# CH32V00x_Touch_Kit.net
KiCad netlist of a schematic drawn in Altium Designer
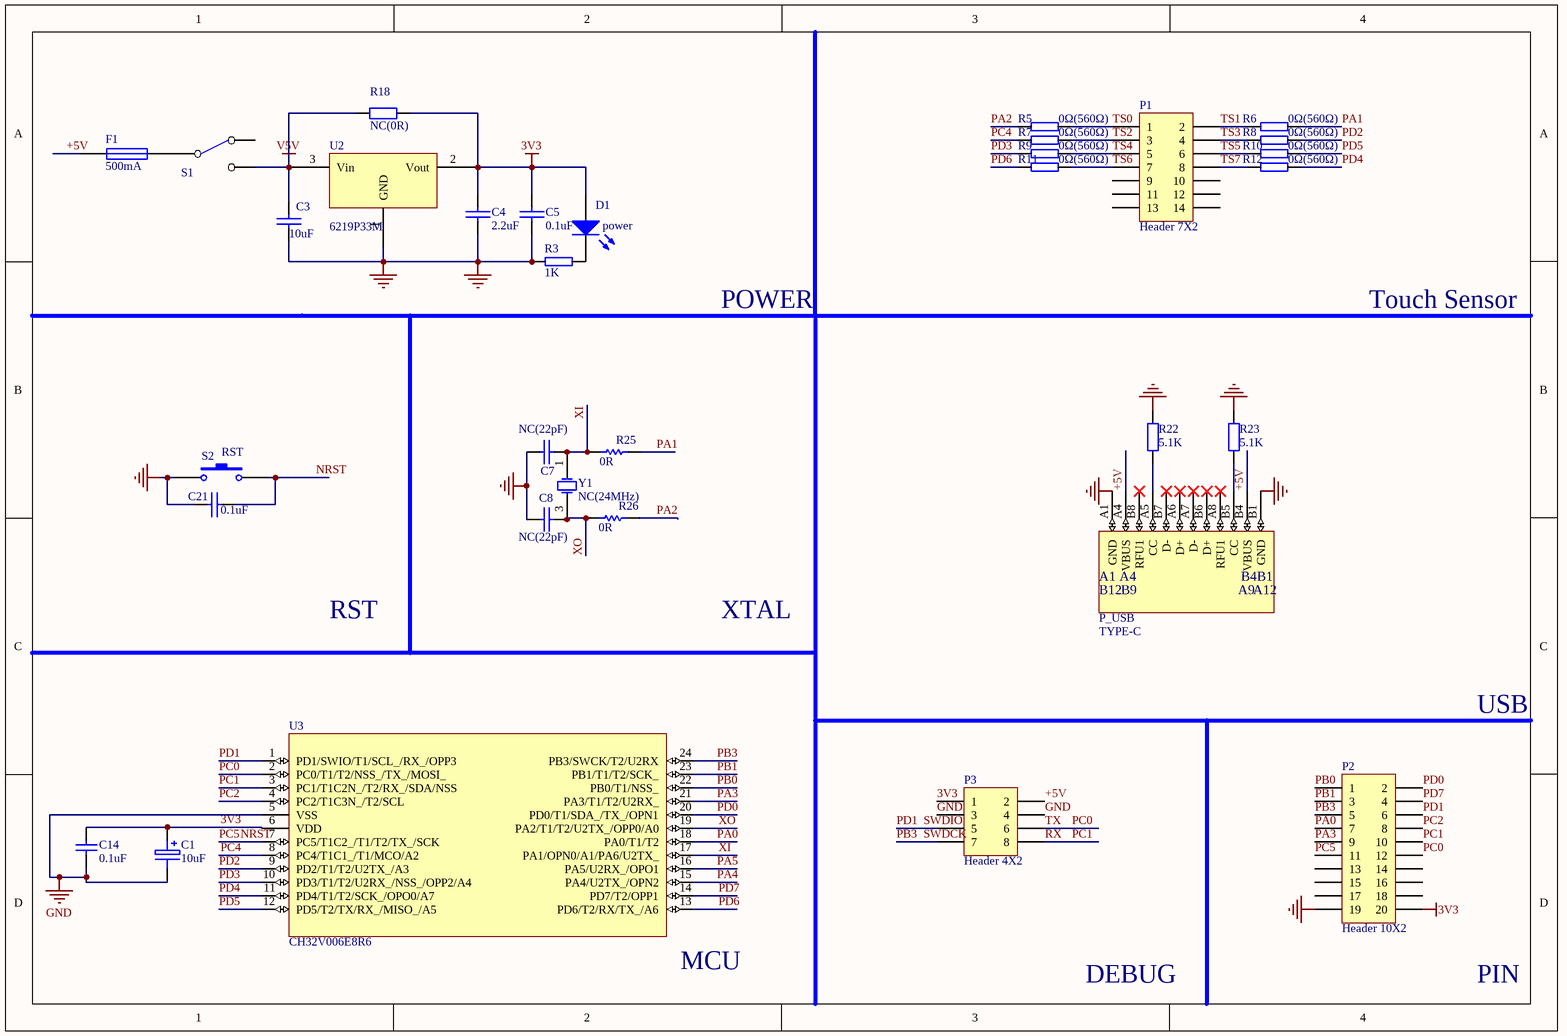
[diagram p0: CH32V00x_Touch_Kit.SchDoc]

(export (version "E")
  (design (tool "Eeschema 10.0.6"))
  (components
    (comp (ref "C1") (value "10uF") (footprint "CASE-A_3216") (libsource (lib "电阻电容") (part "T-A/4.7uF/16V")))
    (comp (ref "C3")
      (value "10uF")
      (footprint "0603_C")
      (description "Capacitor")
      (libsource (lib "") (part "CAP_1"))
    )
    (comp (ref "C4")
      (value "2.2uF")
      (footprint "0402_C")
      (description "Capacitor")
      (libsource (lib "") (part "CAP_1"))
    )
    (comp (ref "C5")
      (value "0.1uF")
      (footprint "0402_C")
      (description "Capacitor")
      (libsource (lib "") (part "CAP_1"))
    )
    (comp (ref "C7")
      (value "NC(22pF)")
      (footprint "0402_C")
      (description "Capacitor")
      (libsource (lib "") (part "CAP_1"))
    )
    (comp (ref "C8")
      (value "NC(22pF)")
      (footprint "0402_C")
      (description "Capacitor")
      (libsource (lib "") (part "CAP_1"))
    )
    (comp (ref "C14")
      (value "0.1uF")
      (footprint "0402_C")
      (description "Capacitor")
      (fields (field (name "PUBLISHER") "Altium Limited"))
      (libsource (lib "*") (part "Cap"))
    )
    (comp (ref "C21")
      (value "0.1uF")
      (footprint "0402_C")
      (description "Capacitor")
      (libsource (lib "*") (part "CAP"))
    )
    (comp (ref "D1")
      (value "power")
      (footprint "0603+")
      (description "Typical INFRARED GaAs LED")
      (fields (field (name "PUBLISHER") "Altium Limited"))
      (libsource (lib "*") (part "LED0"))
    )
    (comp (ref "F1")
      (value "500mA")
      (footprint "0603")
      (description "Fuse")
      (libsource (lib "wch_sch_others") (part "FUSE1"))
    )
    (comp (ref "P1")
      (value "Header 7X2")
      (footprint "HDR-TH_14P-P2.54-H-M-R2-C10-S2.54")
      (description "Header, 7-Pin, Dual row")
      (fields (field (name "PUBLISHER") "Altium Limited"))
      (libsource (lib "Miscellaneous Connectors") (part "Header 7X2"))
    )
    (comp (ref "P2")
      (value "Header 10X2")
      (footprint "HDR-TH_20P-P2.54-H-M-R2-C10-S2.54")
      (description "Header, 10-Pin, Dual row")
      (fields (field (name "PUBLISHER") "Altium Limited"))
      (libsource (lib "Miscellaneous Connectors") (part "Header 10X2"))
    )
    (comp (ref "P3")
      (value "Header 4X2")
      (footprint "IDC8-2.54mm")
      (description "Header, 4-Pin, Dual row")
      (fields (field (name "PUBLISHER") "Altium Limited"))
      (libsource (lib "Miscellaneous Connectors") (part "Header 4X2"))
    )
    (comp (ref "P_USB")
      (value "TYPE-C")
      (footprint "TYPE-C-Receptacle-2.0")
      (libsource (lib "*") (part "TYPE-C1"))
    )
    (comp (ref "R3") (value "1K") (footprint "0402") (libsource (lib "wch_sch_others") (part "RES")))
    (comp (ref "R5") (value "0Ω(560Ω)") (footprint "0402") (libsource (lib "wch_sch_others") (part "RES")))
    (comp (ref "R6") (value "0Ω(560Ω)") (footprint "0402") (libsource (lib "wch_sch_others") (part "RES")))
    (comp (ref "R7") (value "0Ω(560Ω)") (footprint "0402") (libsource (lib "wch_sch_others") (part "RES")))
    (comp (ref "R8") (value "0Ω(560Ω)") (footprint "0402") (libsource (lib "wch_sch_others") (part "RES")))
    (comp (ref "R9") (value "0Ω(560Ω)") (footprint "0402") (libsource (lib "wch_sch_others") (part "RES")))
    (comp (ref "R10") (value "0Ω(560Ω)") (footprint "0402") (libsource (lib "wch_sch_others") (part "RES")))
    (comp (ref "R11") (value "0Ω(560Ω)") (footprint "0402") (libsource (lib "wch_sch_others") (part "RES")))
    (comp (ref "R12") (value "0Ω(560Ω)") (footprint "0402") (libsource (lib "wch_sch_others") (part "RES")))
    (comp (ref "R18")
      (value "NC(0R)")
      (footprint "0402")
      (description "Resistor")
      (fields (field (name "PUBLISHER") "Altium Limited"))
      (libsource (lib "Miscellaneous Devices") (part "Res2"))
    )
    (comp (ref "R22")
      (value "5.1K")
      (footprint "0402")
      (description "Resistor")
      (libsource (lib "") (part "Res2_1"))
    )
    (comp (ref "R23")
      (value "5.1K")
      (footprint "0402")
      (description "Resistor")
      (libsource (lib "") (part "Res2_1"))
    )
    (comp (ref "R25")
      (value "0R")
      (footprint "0402")
      (description "Semiconductor Resistor")
      (fields (field (name "PUBLISHER") "Altium Limited"))
      (libsource (lib "*") (part "Res Semi"))
    )
    (comp (ref "R26")
      (value "0R")
      (footprint "0402")
      (description "Semiconductor Resistor")
      (fields (field (name "PUBLISHER") "Altium Limited"))
      (libsource (lib "*") (part "Res Semi"))
    )
    (comp (ref "S1") (value "SW SPDT") (footprint "SW1") (libsource (lib "*") (part "SW SPDT")))
    (comp (ref "S2")
      (value "RST")
      (footprint "SMD_6.1x3.65x2.5mm-KEY")
      (description "Switch")
      (fields (field (name "PUBLISHER") "Altium Limited"))
      (libsource (lib "*") (part "SW-PB"))
    )
    (comp (ref "U2")
      (value "6219P33M")
      (footprint "SOT-23")
      (libsource (lib "wch_sch_others") (part "6219P33M"))
    )
    (comp (ref "U3")
      (value "CH32V006E8R6")
      (footprint "QSOP24")
      (description "RISC-V MCU, 48MHz, ADC/OPA/CMP/2*UART/I2C/SPI")
      (libsource (lib "CHXXX") (part "CH32V006E8R6"))
    )
    (comp (ref "Y1")
      (value "NC(24MHz)")
      (footprint "XT3225")
      (description "Crystal Oscillator")
      (fields (field (name "PUBLISHER") "Altium Limited"))
      (libsource (lib "*") (part "XTAL"))
    )
  )
  (nets
    (net (code "1") (name "/+5V") (class "Default")
      (node (ref "F1") (pin "1") (pinfunction "1_1") (pintype "passive"))
      (node (ref "P3") (pin "2") (pinfunction "2_2") (pintype "passive"))
      (node (ref "P_USB") (pin "A4") (pinfunction "VBUS_A4") (pintype "bidirectional"))
      (node (ref "P_USB") (pin "B4") (pinfunction "VBUS_B4") (pintype "bidirectional"))
    )
    (net (code "2") (name "/NRST") (class "Default")
      (node (ref "C21") (pin "2") (pinfunction "2_2") (pintype "passive"))
      (node (ref "P2") (pin "11") (pinfunction "11_11") (pintype "passive"))
      (node (ref "S2") (pin "2") (pinfunction "2_2") (pintype "passive"))
      (node (ref "U3") (pin "7") (pinfunction "PC5/T1C2_/T1/T2/TX_/SCK_7") (pintype "bidirectional"))
    )
    (net (code "3") (name "/PA0") (class "Default")
      (node (ref "P2") (pin "7") (pinfunction "7_7") (pintype "passive"))
      (node (ref "U3") (pin "18") (pinfunction "PA0/T1/T2_18") (pintype "bidirectional"))
    )
    (net (code "4") (name "/PA1") (class "Default")
      (node (ref "R25") (pin "2") (pinfunction "2_2") (pintype "passive"))
      (node (ref "R6") (pin "2") (pintype "passive"))
    )
    (net (code "5") (name "/PA2") (class "Default")
      (node (ref "R26") (pin "2") (pinfunction "2_2") (pintype "passive"))
      (node (ref "R5") (pin "1") (pintype "passive"))
    )
    (net (code "6") (name "/PA3") (class "Default")
      (node (ref "P2") (pin "9") (pinfunction "9_9") (pintype "passive"))
      (node (ref "U3") (pin "21") (pinfunction "PA3/T1/T2/U2RX__21") (pintype "bidirectional"))
    )
    (net (code "7") (name "/PA4") (class "Default")
      (node (ref "U3") (pin "15") (pinfunction "PA4/U2TX_/OPN2_15") (pintype "bidirectional"))
    )
    (net (code "8") (name "/PA5") (class "Default")
      (node (ref "U3") (pin "16") (pinfunction "PA5/U2RX_/OPO1_16") (pintype "bidirectional"))
    )
    (net (code "9") (name "/PB0") (class "Default")
      (node (ref "P2") (pin "1") (pinfunction "1_1") (pintype "passive"))
      (node (ref "U3") (pin "22") (pinfunction "PB0/T1/NSS__22") (pintype "bidirectional"))
    )
    (net (code "10") (name "/PB1") (class "Default")
      (node (ref "P2") (pin "3") (pinfunction "3_3") (pintype "passive"))
      (node (ref "U3") (pin "23") (pinfunction "PB1/T1/T2/SCK__23") (pintype "bidirectional"))
    )
    (net (code "11") (name "/PB3") (class "Default")
      (node (ref "P2") (pin "5") (pinfunction "5_5") (pintype "passive"))
      (node (ref "P3") (pin "7") (pinfunction "7_7") (pintype "passive"))
      (node (ref "U3") (pin "24") (pinfunction "PB3/SWCK/T2/U2RX_24") (pintype "bidirectional"))
    )
    (net (code "12") (name "/PC0") (class "Default")
      (node (ref "P2") (pin "12") (pinfunction "12_12") (pintype "passive"))
      (node (ref "P3") (pin "6") (pinfunction "6_6") (pintype "passive"))
      (node (ref "U3") (pin "2") (pinfunction "PC0/T1/T2/NSS_/TX_/MOSI__2") (pintype "bidirectional"))
    )
    (net (code "13") (name "/PC1") (class "Default")
      (node (ref "P2") (pin "10") (pinfunction "10_10") (pintype "passive"))
      (node (ref "P3") (pin "8") (pinfunction "8_8") (pintype "passive"))
      (node (ref "U3") (pin "3") (pinfunction "PC1/T1C2N_/T2/RX_/SDA/NSS_3") (pintype "bidirectional"))
    )
    (net (code "14") (name "/PC2") (class "Default")
      (node (ref "P2") (pin "8") (pinfunction "8_8") (pintype "passive"))
      (node (ref "U3") (pin "4") (pinfunction "PC2/T1C3N_/T2/SCL_4") (pintype "bidirectional"))
    )
    (net (code "15") (name "/PC4") (class "Default")
      (node (ref "R7") (pin "1") (pintype "passive"))
      (node (ref "U3") (pin "8") (pinfunction "PC4/T1C1_/T1/MCO/A2_8") (pintype "bidirectional"))
    )
    (net (code "16") (name "/PD0") (class "Default")
      (node (ref "P2") (pin "2") (pinfunction "2_2") (pintype "passive"))
      (node (ref "U3") (pin "20") (pinfunction "PD0/T1/SDA_/TX_/OPN1_20") (pintype "bidirectional"))
    )
    (net (code "17") (name "/PD1") (class "Default")
      (node (ref "P2") (pin "6") (pinfunction "6_6") (pintype "passive"))
      (node (ref "P3") (pin "5") (pinfunction "5_5") (pintype "passive"))
      (node (ref "U3") (pin "1") (pinfunction "PD1/SWIO/T1/SCL_/RX_/OPP3_1") (pintype "bidirectional"))
    )
    (net (code "18") (name "/PD2") (class "Default")
      (node (ref "R8") (pin "2") (pintype "passive"))
      (node (ref "U3") (pin "9") (pinfunction "PD2/T1/T2/U2TX_/A3_9") (pintype "bidirectional"))
    )
    (net (code "19") (name "/PD3") (class "Default")
      (node (ref "R9") (pin "1") (pintype "passive"))
      (node (ref "U3") (pin "10") (pinfunction "PD3/T1/T2/U2RX_/NSS_/OPP2/A4_10") (pintype "bidirectional"))
    )
    (net (code "20") (name "/PD4") (class "Default")
      (node (ref "R12") (pin "2") (pintype "passive"))
      (node (ref "U3") (pin "11") (pinfunction "PD4/T1/T2/SCK_/OPO0/A7_11") (pintype "bidirectional"))
    )
    (net (code "21") (name "/PD5") (class "Default")
      (node (ref "R10") (pin "2") (pintype "passive"))
      (node (ref "U3") (pin "12") (pinfunction "PD5/T2/TX/RX_/MISO_/A5_12") (pintype "bidirectional"))
    )
    (net (code "22") (name "/PD6") (class "Default")
      (node (ref "R11") (pin "1") (pintype "passive"))
      (node (ref "U3") (pin "13") (pinfunction "PD6/T2/RX/TX_/A6_13") (pintype "bidirectional"))
    )
    (net (code "23") (name "/PD7") (class "Default")
      (node (ref "P2") (pin "4") (pinfunction "4_4") (pintype "passive"))
      (node (ref "U3") (pin "14") (pinfunction "PD7/T2/OPP1_14") (pintype "bidirectional"))
    )
    (net (code "24") (name "/TS0") (class "Default")
      (node (ref "P1") (pin "1") (pinfunction "1_1") (pintype "passive"))
      (node (ref "R5") (pin "2") (pintype "passive"))
    )
    (net (code "25") (name "/TS1") (class "Default")
      (node (ref "P1") (pin "2") (pinfunction "2_2") (pintype "passive"))
      (node (ref "R6") (pin "1") (pintype "passive"))
    )
    (net (code "26") (name "/TS2") (class "Default")
      (node (ref "P1") (pin "3") (pinfunction "3_3") (pintype "passive"))
      (node (ref "R7") (pin "2") (pintype "passive"))
    )
    (net (code "27") (name "/TS3") (class "Default")
      (node (ref "P1") (pin "4") (pinfunction "4_4") (pintype "passive"))
      (node (ref "R8") (pin "1") (pintype "passive"))
    )
    (net (code "28") (name "/TS4") (class "Default")
      (node (ref "P1") (pin "5") (pinfunction "5_5") (pintype "passive"))
      (node (ref "R9") (pin "2") (pintype "passive"))
    )
    (net (code "29") (name "/TS5") (class "Default")
      (node (ref "P1") (pin "6") (pinfunction "6_6") (pintype "passive"))
      (node (ref "R10") (pin "1") (pintype "passive"))
    )
    (net (code "30") (name "/TS6") (class "Default")
      (node (ref "P1") (pin "7") (pinfunction "7_7") (pintype "passive"))
      (node (ref "R11") (pin "2") (pintype "passive"))
    )
    (net (code "31") (name "/TS7") (class "Default")
      (node (ref "P1") (pin "8") (pinfunction "8_8") (pintype "passive"))
      (node (ref "R12") (pin "1") (pintype "passive"))
    )
    (net (code "32") (name "/XI") (class "Default")
      (node (ref "C7") (pin "2") (pinfunction "2_2") (pintype "passive"))
      (node (ref "R25") (pin "1") (pinfunction "1_1") (pintype "passive"))
      (node (ref "U3") (pin "17") (pinfunction "PA1/OPN0/A1/PA6/U2TX__17") (pintype "bidirectional"))
      (node (ref "Y1") (pin "1") (pinfunction "OSC1_1") (pintype "passive"))
    )
    (net (code "33") (name "/XO") (class "Default")
      (node (ref "C8") (pin "2") (pinfunction "2_2") (pintype "passive"))
      (node (ref "R26") (pin "1") (pinfunction "1_1") (pintype "passive"))
      (node (ref "U3") (pin "19") (pinfunction "PA2/T1/T2/U2TX_/OPP0/A0_19") (pintype "bidirectional"))
      (node (ref "Y1") (pin "3") (pinfunction "OSC2_3") (pintype "passive"))
    )
    (net (code "34") (name "3V3") (class "Default")
      (node (ref "C1") (pin "1") (pinfunction "1_1") (pintype "passive"))
      (node (ref "C14") (pin "2") (pinfunction "2_2") (pintype "passive"))
      (node (ref "C4") (pin "1") (pinfunction "1_1") (pintype "passive"))
      (node (ref "C5") (pin "1") (pinfunction "1_1") (pintype "passive"))
      (node (ref "D1") (pin "1") (pinfunction "A_1") (pintype "passive"))
      (node (ref "P2") (pin "20") (pinfunction "20_20") (pintype "passive"))
      (node (ref "P3") (pin "1") (pinfunction "1_1") (pintype "passive"))
      (node (ref "R18") (pin "1") (pinfunction "1_1") (pintype "passive"))
      (node (ref "U2") (pin "2") (pinfunction "Vout_2") (pintype "passive"))
      (node (ref "U3") (pin "6") (pinfunction "VDD_6") (pintype "power_in"))
    )
    (net (code "35") (name "GND") (class "Default")
      (node (ref "C1") (pin "2") (pinfunction "2_2") (pintype "passive"))
      (node (ref "C14") (pin "1") (pinfunction "1_1") (pintype "passive"))
      (node (ref "C21") (pin "1") (pinfunction "1_1") (pintype "passive"))
      (node (ref "C3") (pin "2") (pinfunction "2_2") (pintype "passive"))
      (node (ref "C4") (pin "2") (pinfunction "2_2") (pintype "passive"))
      (node (ref "C5") (pin "2") (pinfunction "2_2") (pintype "passive"))
      (node (ref "C7") (pin "1") (pinfunction "1_1") (pintype "passive"))
      (node (ref "C8") (pin "1") (pinfunction "1_1") (pintype "passive"))
      (node (ref "P2") (pin "19") (pinfunction "19_19") (pintype "passive"))
      (node (ref "P3") (pin "3") (pinfunction "3_3") (pintype "passive"))
      (node (ref "P3") (pin "4") (pinfunction "4_4") (pintype "passive"))
      (node (ref "P_USB") (pin "A1") (pinfunction "GND_A1") (pintype "bidirectional"))
      (node (ref "P_USB") (pin "B1") (pinfunction "GND_B1") (pintype "bidirectional"))
      (node (ref "R22") (pin "2") (pinfunction "2_2") (pintype "passive"))
      (node (ref "R23") (pin "2") (pinfunction "2_2") (pintype "passive"))
      (node (ref "R3") (pin "2") (pintype "passive"))
      (node (ref "S2") (pin "1") (pinfunction "1_1") (pintype "passive"))
      (node (ref "U2") (pin "1") (pinfunction "GND_1") (pintype "passive"))
      (node (ref "U3") (pin "5") (pinfunction "VSS_5") (pintype "power_in"))
    )
    (net (code "36") (name "Net-(D1-K)") (class "Default")
      (node (ref "D1") (pin "2") (pinfunction "K_2") (pintype "passive"))
      (node (ref "R3") (pin "1") (pintype "passive"))
    )
    (net (code "37") (name "Net-(P_USB-CC-PadA5)") (class "Default")
      (node (ref "P_USB") (pin "A5") (pinfunction "CC_A5") (pintype "bidirectional"))
      (node (ref "R22") (pin "1") (pinfunction "1_1") (pintype "passive"))
    )
    (net (code "38") (name "Net-(P_USB-CC-PadB5)") (class "Default")
      (node (ref "P_USB") (pin "B5") (pinfunction "CC_B5") (pintype "bidirectional"))
      (node (ref "R23") (pin "1") (pinfunction "1_1") (pintype "passive"))
    )
    (net (code "39") (name "Net-(S1-COMMON)") (class "Default")
      (node (ref "F1") (pin "2") (pinfunction "2_2") (pintype "passive"))
      (node (ref "S1") (pin "1") (pinfunction "COMMON_1") (pintype "passive"))
    )
    (net (code "40") (name "V5V") (class "Default")
      (node (ref "C3") (pin "1") (pinfunction "1_1") (pintype "passive"))
      (node (ref "R18") (pin "2") (pinfunction "2_2") (pintype "passive"))
      (node (ref "S1") (pin "2") (pinfunction "NC_2") (pintype "passive"))
      (node (ref "U2") (pin "3") (pinfunction "Vin_3") (pintype "passive"))
    )
    (net (code "41") (name "unconnected-(P1-Pad9)") (class "Default")
      (node (ref "P1") (pin "9") (pinfunction "9_9") (pintype "passive"))
    )
    (net (code "42") (name "unconnected-(P1-Pad10)") (class "Default")
      (node (ref "P1") (pin "10") (pinfunction "10_10") (pintype "passive"))
    )
    (net (code "43") (name "unconnected-(P1-Pad11)") (class "Default")
      (node (ref "P1") (pin "11") (pinfunction "11_11") (pintype "passive"))
    )
    (net (code "44") (name "unconnected-(P1-Pad12)") (class "Default")
      (node (ref "P1") (pin "12") (pinfunction "12_12") (pintype "passive"))
    )
    (net (code "45") (name "unconnected-(P1-Pad13)") (class "Default")
      (node (ref "P1") (pin "13") (pinfunction "13_13") (pintype "passive"))
    )
    (net (code "46") (name "unconnected-(P1-Pad14)") (class "Default")
      (node (ref "P1") (pin "14") (pinfunction "14_14") (pintype "passive"))
    )
    (net (code "47") (name "unconnected-(P2-Pad13)") (class "Default")
      (node (ref "P2") (pin "13") (pinfunction "13_13") (pintype "passive"))
    )
    (net (code "48") (name "unconnected-(P2-Pad14)") (class "Default")
      (node (ref "P2") (pin "14") (pinfunction "14_14") (pintype "passive"))
    )
    (net (code "49") (name "unconnected-(P2-Pad15)") (class "Default")
      (node (ref "P2") (pin "15") (pinfunction "15_15") (pintype "passive"))
    )
    (net (code "50") (name "unconnected-(P2-Pad16)") (class "Default")
      (node (ref "P2") (pin "16") (pinfunction "16_16") (pintype "passive"))
    )
    (net (code "51") (name "unconnected-(P2-Pad17)") (class "Default")
      (node (ref "P2") (pin "17") (pinfunction "17_17") (pintype "passive"))
    )
    (net (code "52") (name "unconnected-(P2-Pad18)") (class "Default")
      (node (ref "P2") (pin "18") (pinfunction "18_18") (pintype "passive"))
    )
    (net (code "53") (name "unconnected-(P_USB-D+-PadA6)") (class "Default")
      (node (ref "P_USB") (pin "A6") (pinfunction "D+_A6") (pintype "bidirectional+no_connect"))
    )
    (net (code "54") (name "unconnected-(P_USB-D+-PadB6)") (class "Default")
      (node (ref "P_USB") (pin "B6") (pinfunction "D+_B6") (pintype "bidirectional+no_connect"))
    )
    (net (code "55") (name "unconnected-(P_USB-D--PadA7)") (class "Default")
      (node (ref "P_USB") (pin "A7") (pinfunction "D-_A7") (pintype "bidirectional+no_connect"))
    )
    (net (code "56") (name "unconnected-(P_USB-D--PadB7)") (class "Default")
      (node (ref "P_USB") (pin "B7") (pinfunction "D-_B7") (pintype "bidirectional+no_connect"))
    )
    (net (code "57") (name "unconnected-(P_USB-RFU1-PadA8)") (class "Default")
      (node (ref "P_USB") (pin "A8") (pinfunction "RFU1_A8") (pintype "bidirectional+no_connect"))
    )
    (net (code "58") (name "unconnected-(P_USB-RFU1-PadB8)") (class "Default")
      (node (ref "P_USB") (pin "B8") (pinfunction "RFU1_B8") (pintype "bidirectional+no_connect"))
    )
    (net (code "59") (name "unconnected-(S1-NO-Pad3)") (class "Default")
      (node (ref "S1") (pin "3") (pinfunction "NO_3") (pintype "passive"))
    )
  )
)
